# Traction_Control_Standalone.net
KiCad netlist of a schematic drawn in EAGLE
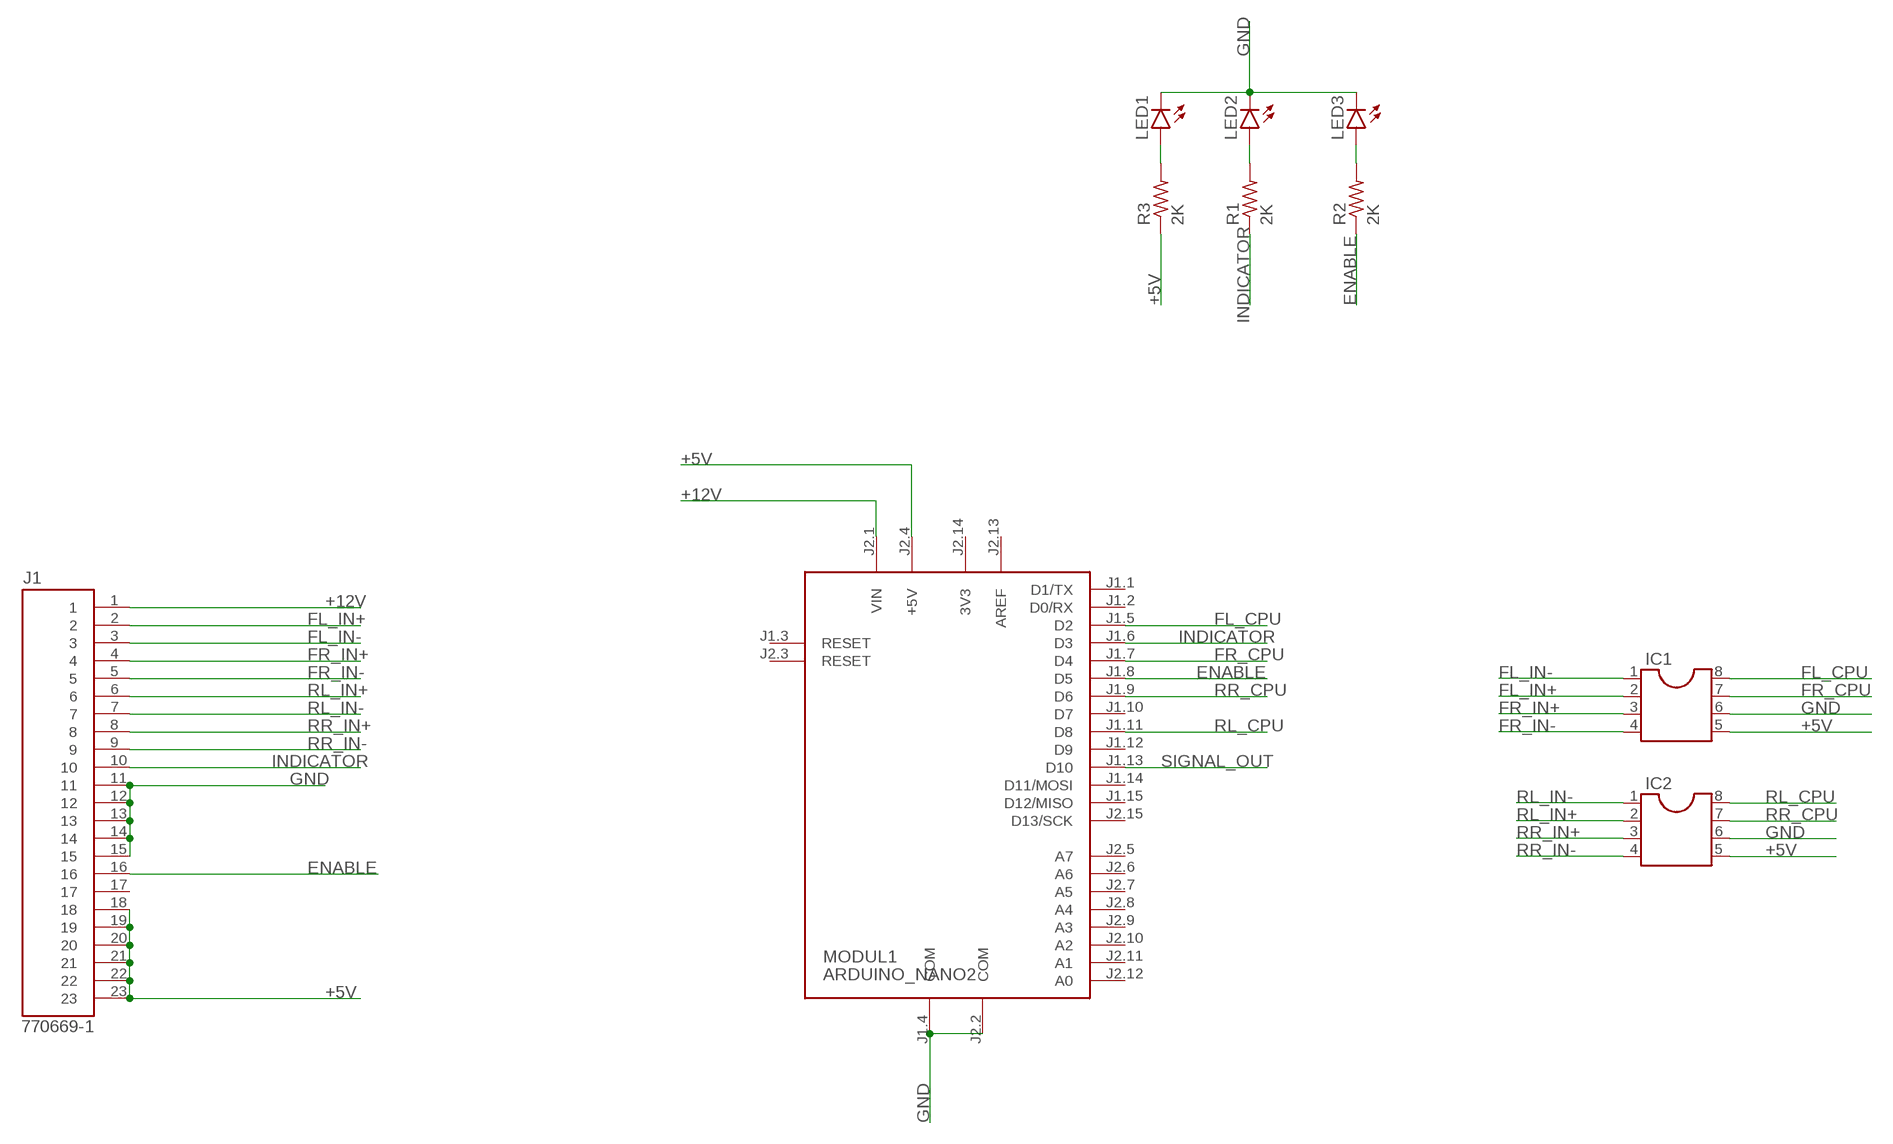
[diagram p0: schematic, sheet 1]

(export (version "E")
  (design (tool "Eeschema 10.0.6"))
  (components
    (comp (ref "IC1")
      (value "DIL8S")
      (footprint "eagle-import:SOCKET-08")
      (libsource (lib "eagle-import") (part "DIL8S"))
    )
    (comp (ref "IC2")
      (value "DIL8S")
      (footprint "eagle-import:SOCKET-08")
      (libsource (lib "eagle-import") (part "DIL8S"))
    )
    (comp (ref "J1")
      (value "770669-1")
      (footprint "eagle-import:TE_770669-1")
      (fields (field (name "MF") "TE Connectivity"))
      (libsource (lib "eagle-import") (part "770669-1"))
    )
    (comp (ref "LED1")
      (value "LEDCHIP-LED0805")
      (footprint "eagle-import:CHIP-LED0805")
      (libsource (lib "eagle-import") (part "LEDCHIP-LED0805"))
    )
    (comp (ref "LED2")
      (value "LEDCHIP-LED0805")
      (footprint "eagle-import:CHIP-LED0805")
      (libsource (lib "eagle-import") (part "LEDCHIP-LED0805"))
    )
    (comp (ref "LED3")
      (value "LEDCHIP-LED0805")
      (footprint "eagle-import:CHIP-LED0805")
      (libsource (lib "eagle-import") (part "LEDCHIP-LED0805"))
    )
    (comp (ref "MODUL1")
      (value "ARDUINO_NANO2")
      (footprint "eagle-import:ARDUINO_NANO2")
      (libsource (lib "eagle-import") (part "ARDUINO_NANO2"))
    )
    (comp (ref "R1")
      (value "2K")
      (footprint "eagle-import:R0805")
      (libsource (lib "eagle-import") (part "R-US_R0805"))
    )
    (comp (ref "R2")
      (value "2K")
      (footprint "eagle-import:R0805")
      (libsource (lib "eagle-import") (part "R-US_R0805"))
    )
    (comp (ref "R3")
      (value "2K")
      (footprint "eagle-import:R0805")
      (libsource (lib "eagle-import") (part "R-US_R0805"))
    )
  )
  (nets
    (net (code "1") (name "/+5V") (class "Default")
      (node (ref "IC1") (pin "5") (pinfunction "5_5") (pintype "passive"))
      (node (ref "IC2") (pin "5") (pinfunction "5_5") (pintype "passive"))
      (node (ref "J1") (pin "18") (pinfunction "18_18") (pintype "passive"))
      (node (ref "J1") (pin "19") (pinfunction "19_19") (pintype "passive"))
      (node (ref "J1") (pin "20") (pinfunction "20_20") (pintype "passive"))
      (node (ref "J1") (pin "21") (pinfunction "21_21") (pintype "passive"))
      (node (ref "J1") (pin "22") (pinfunction "22_22") (pintype "passive"))
      (node (ref "J1") (pin "23") (pinfunction "23_23") (pintype "passive"))
      (node (ref "MODUL1") (pin "J2.4") (pinfunction "+5V_J2.4") (pintype "power_in"))
      (node (ref "R3") (pin "1") (pinfunction "1_1") (pintype "passive"))
    )
    (net (code "2") (name "/+12V") (class "Default")
      (node (ref "J1") (pin "1") (pinfunction "1_1") (pintype "passive"))
      (node (ref "MODUL1") (pin "J2.1") (pinfunction "VIN_J2.1") (pintype "power_in"))
    )
    (net (code "3") (name "/3V3") (class "Default")
      (node (ref "MODUL1") (pin "J2.14") (pinfunction "3V3_J2.14") (pintype "power_in"))
    )
    (net (code "4") (name "/AREF") (class "Default")
      (node (ref "MODUL1") (pin "J2.13") (pinfunction "AREF_J2.13") (pintype "power_in"))
    )
    (net (code "5") (name "/ENABLE") (class "Default")
      (node (ref "J1") (pin "16") (pinfunction "16_16") (pintype "passive"))
      (node (ref "MODUL1") (pin "J1.8") (pinfunction "D5_J1.8") (pintype "bidirectional"))
      (node (ref "R2") (pin "1") (pinfunction "1_1") (pintype "passive"))
    )
    (net (code "6") (name "/FL_CPU") (class "Default")
      (node (ref "IC1") (pin "8") (pinfunction "8_8") (pintype "passive"))
      (node (ref "MODUL1") (pin "J1.5") (pinfunction "D2_J1.5") (pintype "bidirectional"))
    )
    (net (code "7") (name "/FL_IN+") (class "Default")
      (node (ref "IC1") (pin "2") (pinfunction "2_2") (pintype "passive"))
      (node (ref "J1") (pin "2") (pinfunction "2_2") (pintype "passive"))
    )
    (net (code "8") (name "/FL_IN-") (class "Default")
      (node (ref "IC1") (pin "1") (pinfunction "1_1") (pintype "passive"))
      (node (ref "J1") (pin "3") (pinfunction "3_3") (pintype "passive"))
    )
    (net (code "9") (name "/FR_CPU") (class "Default")
      (node (ref "IC1") (pin "7") (pinfunction "7_7") (pintype "passive"))
      (node (ref "MODUL1") (pin "J1.7") (pinfunction "D4_J1.7") (pintype "bidirectional"))
    )
    (net (code "10") (name "/FR_IN+") (class "Default")
      (node (ref "IC1") (pin "3") (pinfunction "3_3") (pintype "passive"))
      (node (ref "J1") (pin "4") (pinfunction "4_4") (pintype "passive"))
    )
    (net (code "11") (name "/FR_IN-") (class "Default")
      (node (ref "IC1") (pin "4") (pinfunction "4_4") (pintype "passive"))
      (node (ref "J1") (pin "5") (pinfunction "5_5") (pintype "passive"))
    )
    (net (code "12") (name "/GND") (class "Default")
      (node (ref "IC1") (pin "6") (pinfunction "6_6") (pintype "passive"))
      (node (ref "IC2") (pin "6") (pinfunction "6_6") (pintype "passive"))
      (node (ref "J1") (pin "11") (pinfunction "11_11") (pintype "passive"))
      (node (ref "J1") (pin "12") (pinfunction "12_12") (pintype "passive"))
      (node (ref "J1") (pin "13") (pinfunction "13_13") (pintype "passive"))
      (node (ref "J1") (pin "14") (pinfunction "14_14") (pintype "passive"))
      (node (ref "J1") (pin "15") (pinfunction "15_15") (pintype "passive"))
      (node (ref "LED1") (pin "C") (pinfunction "C_C") (pintype "passive"))
      (node (ref "LED2") (pin "C") (pinfunction "C_C") (pintype "passive"))
      (node (ref "LED3") (pin "C") (pinfunction "C_C") (pintype "passive"))
      (node (ref "MODUL1") (pin "J1.4") (pinfunction "COM_J1.4") (pintype "power_in"))
      (node (ref "MODUL1") (pin "J2.2") (pinfunction "COM_J2.2") (pintype "power_in"))
    )
    (net (code "13") (name "/INDICATOR") (class "Default")
      (node (ref "J1") (pin "10") (pinfunction "10_10") (pintype "passive"))
      (node (ref "MODUL1") (pin "J1.6") (pinfunction "D3_J1.6") (pintype "bidirectional"))
      (node (ref "R1") (pin "1") (pinfunction "1_1") (pintype "passive"))
    )
    (net (code "14") (name "/RL_CPU") (class "Default")
      (node (ref "IC2") (pin "8") (pinfunction "8_8") (pintype "passive"))
      (node (ref "MODUL1") (pin "J1.11") (pinfunction "D8_J1.11") (pintype "bidirectional"))
    )
    (net (code "15") (name "/RL_IN+") (class "Default")
      (node (ref "IC2") (pin "2") (pinfunction "2_2") (pintype "passive"))
      (node (ref "J1") (pin "6") (pinfunction "6_6") (pintype "passive"))
    )
    (net (code "16") (name "/RL_IN-") (class "Default")
      (node (ref "IC2") (pin "1") (pinfunction "1_1") (pintype "passive"))
      (node (ref "J1") (pin "7") (pinfunction "7_7") (pintype "passive"))
    )
    (net (code "17") (name "/RR_CPU") (class "Default")
      (node (ref "IC2") (pin "7") (pinfunction "7_7") (pintype "passive"))
      (node (ref "MODUL1") (pin "J1.9") (pinfunction "D6_J1.9") (pintype "bidirectional"))
    )
    (net (code "18") (name "/RR_IN+") (class "Default")
      (node (ref "IC2") (pin "3") (pinfunction "3_3") (pintype "passive"))
      (node (ref "J1") (pin "8") (pinfunction "8_8") (pintype "passive"))
    )
    (net (code "19") (name "/RR_IN-") (class "Default")
      (node (ref "IC2") (pin "4") (pinfunction "4_4") (pintype "passive"))
      (node (ref "J1") (pin "9") (pinfunction "9_9") (pintype "passive"))
    )
    (net (code "20") (name "/SIGNAL_OUT") (class "Default")
      (node (ref "MODUL1") (pin "J1.13") (pinfunction "D10_J1.13") (pintype "bidirectional"))
    )
    (net (code "21") (name "Net-(LED1-PadA)") (class "Default")
      (node (ref "LED1") (pin "A") (pinfunction "A_A") (pintype "passive"))
      (node (ref "R3") (pin "2") (pinfunction "2_2") (pintype "passive"))
    )
    (net (code "22") (name "Net-(LED2-PadA)") (class "Default")
      (node (ref "LED2") (pin "A") (pinfunction "A_A") (pintype "passive"))
      (node (ref "R1") (pin "2") (pinfunction "2_2") (pintype "passive"))
    )
    (net (code "23") (name "Net-(LED3-PadA)") (class "Default")
      (node (ref "LED3") (pin "A") (pinfunction "A_A") (pintype "passive"))
      (node (ref "R2") (pin "2") (pinfunction "2_2") (pintype "passive"))
    )
    (net (code "24") (name "unconnected-(J1-Pad17)") (class "Default")
      (node (ref "J1") (pin "17") (pinfunction "17_17") (pintype "passive"))
    )
    (net (code "25") (name "unconnected-(MODUL1-A0-PadJ2.12)") (class "Default")
      (node (ref "MODUL1") (pin "J2.12") (pinfunction "A0_J2.12") (pintype "bidirectional"))
    )
    (net (code "26") (name "unconnected-(MODUL1-A1-PadJ2.11)") (class "Default")
      (node (ref "MODUL1") (pin "J2.11") (pinfunction "A1_J2.11") (pintype "bidirectional"))
    )
    (net (code "27") (name "unconnected-(MODUL1-A2-PadJ2.10)") (class "Default")
      (node (ref "MODUL1") (pin "J2.10") (pinfunction "A2_J2.10") (pintype "bidirectional"))
    )
    (net (code "28") (name "unconnected-(MODUL1-A3-PadJ2.9)") (class "Default")
      (node (ref "MODUL1") (pin "J2.9") (pinfunction "A3_J2.9") (pintype "bidirectional"))
    )
    (net (code "29") (name "unconnected-(MODUL1-A4-PadJ2.8)") (class "Default")
      (node (ref "MODUL1") (pin "J2.8") (pinfunction "A4_J2.8") (pintype "bidirectional"))
    )
    (net (code "30") (name "unconnected-(MODUL1-A5-PadJ2.7)") (class "Default")
      (node (ref "MODUL1") (pin "J2.7") (pinfunction "A5_J2.7") (pintype "bidirectional"))
    )
    (net (code "31") (name "unconnected-(MODUL1-A6-PadJ2.6)") (class "Default")
      (node (ref "MODUL1") (pin "J2.6") (pinfunction "A6_J2.6") (pintype "bidirectional"))
    )
    (net (code "32") (name "unconnected-(MODUL1-A7-PadJ2.5)") (class "Default")
      (node (ref "MODUL1") (pin "J2.5") (pinfunction "A7_J2.5") (pintype "bidirectional"))
    )
    (net (code "33") (name "unconnected-(MODUL1-D0{slash}RX-PadJ1.2)") (class "Default")
      (node (ref "MODUL1") (pin "J1.2") (pinfunction "D0/RX_J1.2") (pintype "bidirectional"))
    )
    (net (code "34") (name "unconnected-(MODUL1-D1{slash}TX-PadJ1.1)") (class "Default")
      (node (ref "MODUL1") (pin "J1.1") (pinfunction "D1/TX_J1.1") (pintype "bidirectional"))
    )
    (net (code "35") (name "unconnected-(MODUL1-D7-PadJ1.10)") (class "Default")
      (node (ref "MODUL1") (pin "J1.10") (pinfunction "D7_J1.10") (pintype "bidirectional"))
    )
    (net (code "36") (name "unconnected-(MODUL1-D9-PadJ1.12)") (class "Default")
      (node (ref "MODUL1") (pin "J1.12") (pinfunction "D9_J1.12") (pintype "bidirectional"))
    )
    (net (code "37") (name "unconnected-(MODUL1-D11{slash}MOSI-PadJ1.14)") (class "Default")
      (node (ref "MODUL1") (pin "J1.14") (pinfunction "D11/MOSI_J1.14") (pintype "bidirectional"))
    )
    (net (code "38") (name "unconnected-(MODUL1-D12{slash}MISO-PadJ1.15)") (class "Default")
      (node (ref "MODUL1") (pin "J1.15") (pinfunction "D12/MISO_J1.15") (pintype "bidirectional"))
    )
    (net (code "39") (name "unconnected-(MODUL1-D13{slash}SCK-PadJ2.15)") (class "Default")
      (node (ref "MODUL1") (pin "J2.15") (pinfunction "D13/SCK_J2.15") (pintype "bidirectional"))
    )
    (net (code "40") (name "unconnected-(MODUL1-RESET-PadJ1.3)") (class "Default")
      (node (ref "MODUL1") (pin "J1.3") (pinfunction "RESET_J1.3") (pintype "bidirectional"))
    )
    (net (code "41") (name "unconnected-(MODUL1-RESET-PadJ2.3)") (class "Default")
      (node (ref "MODUL1") (pin "J2.3") (pinfunction "RESET_J2.3") (pintype "bidirectional"))
    )
  )
)
